# AnalogSupplies.net
KiCad netlist of a schematic drawn in Altium Designer
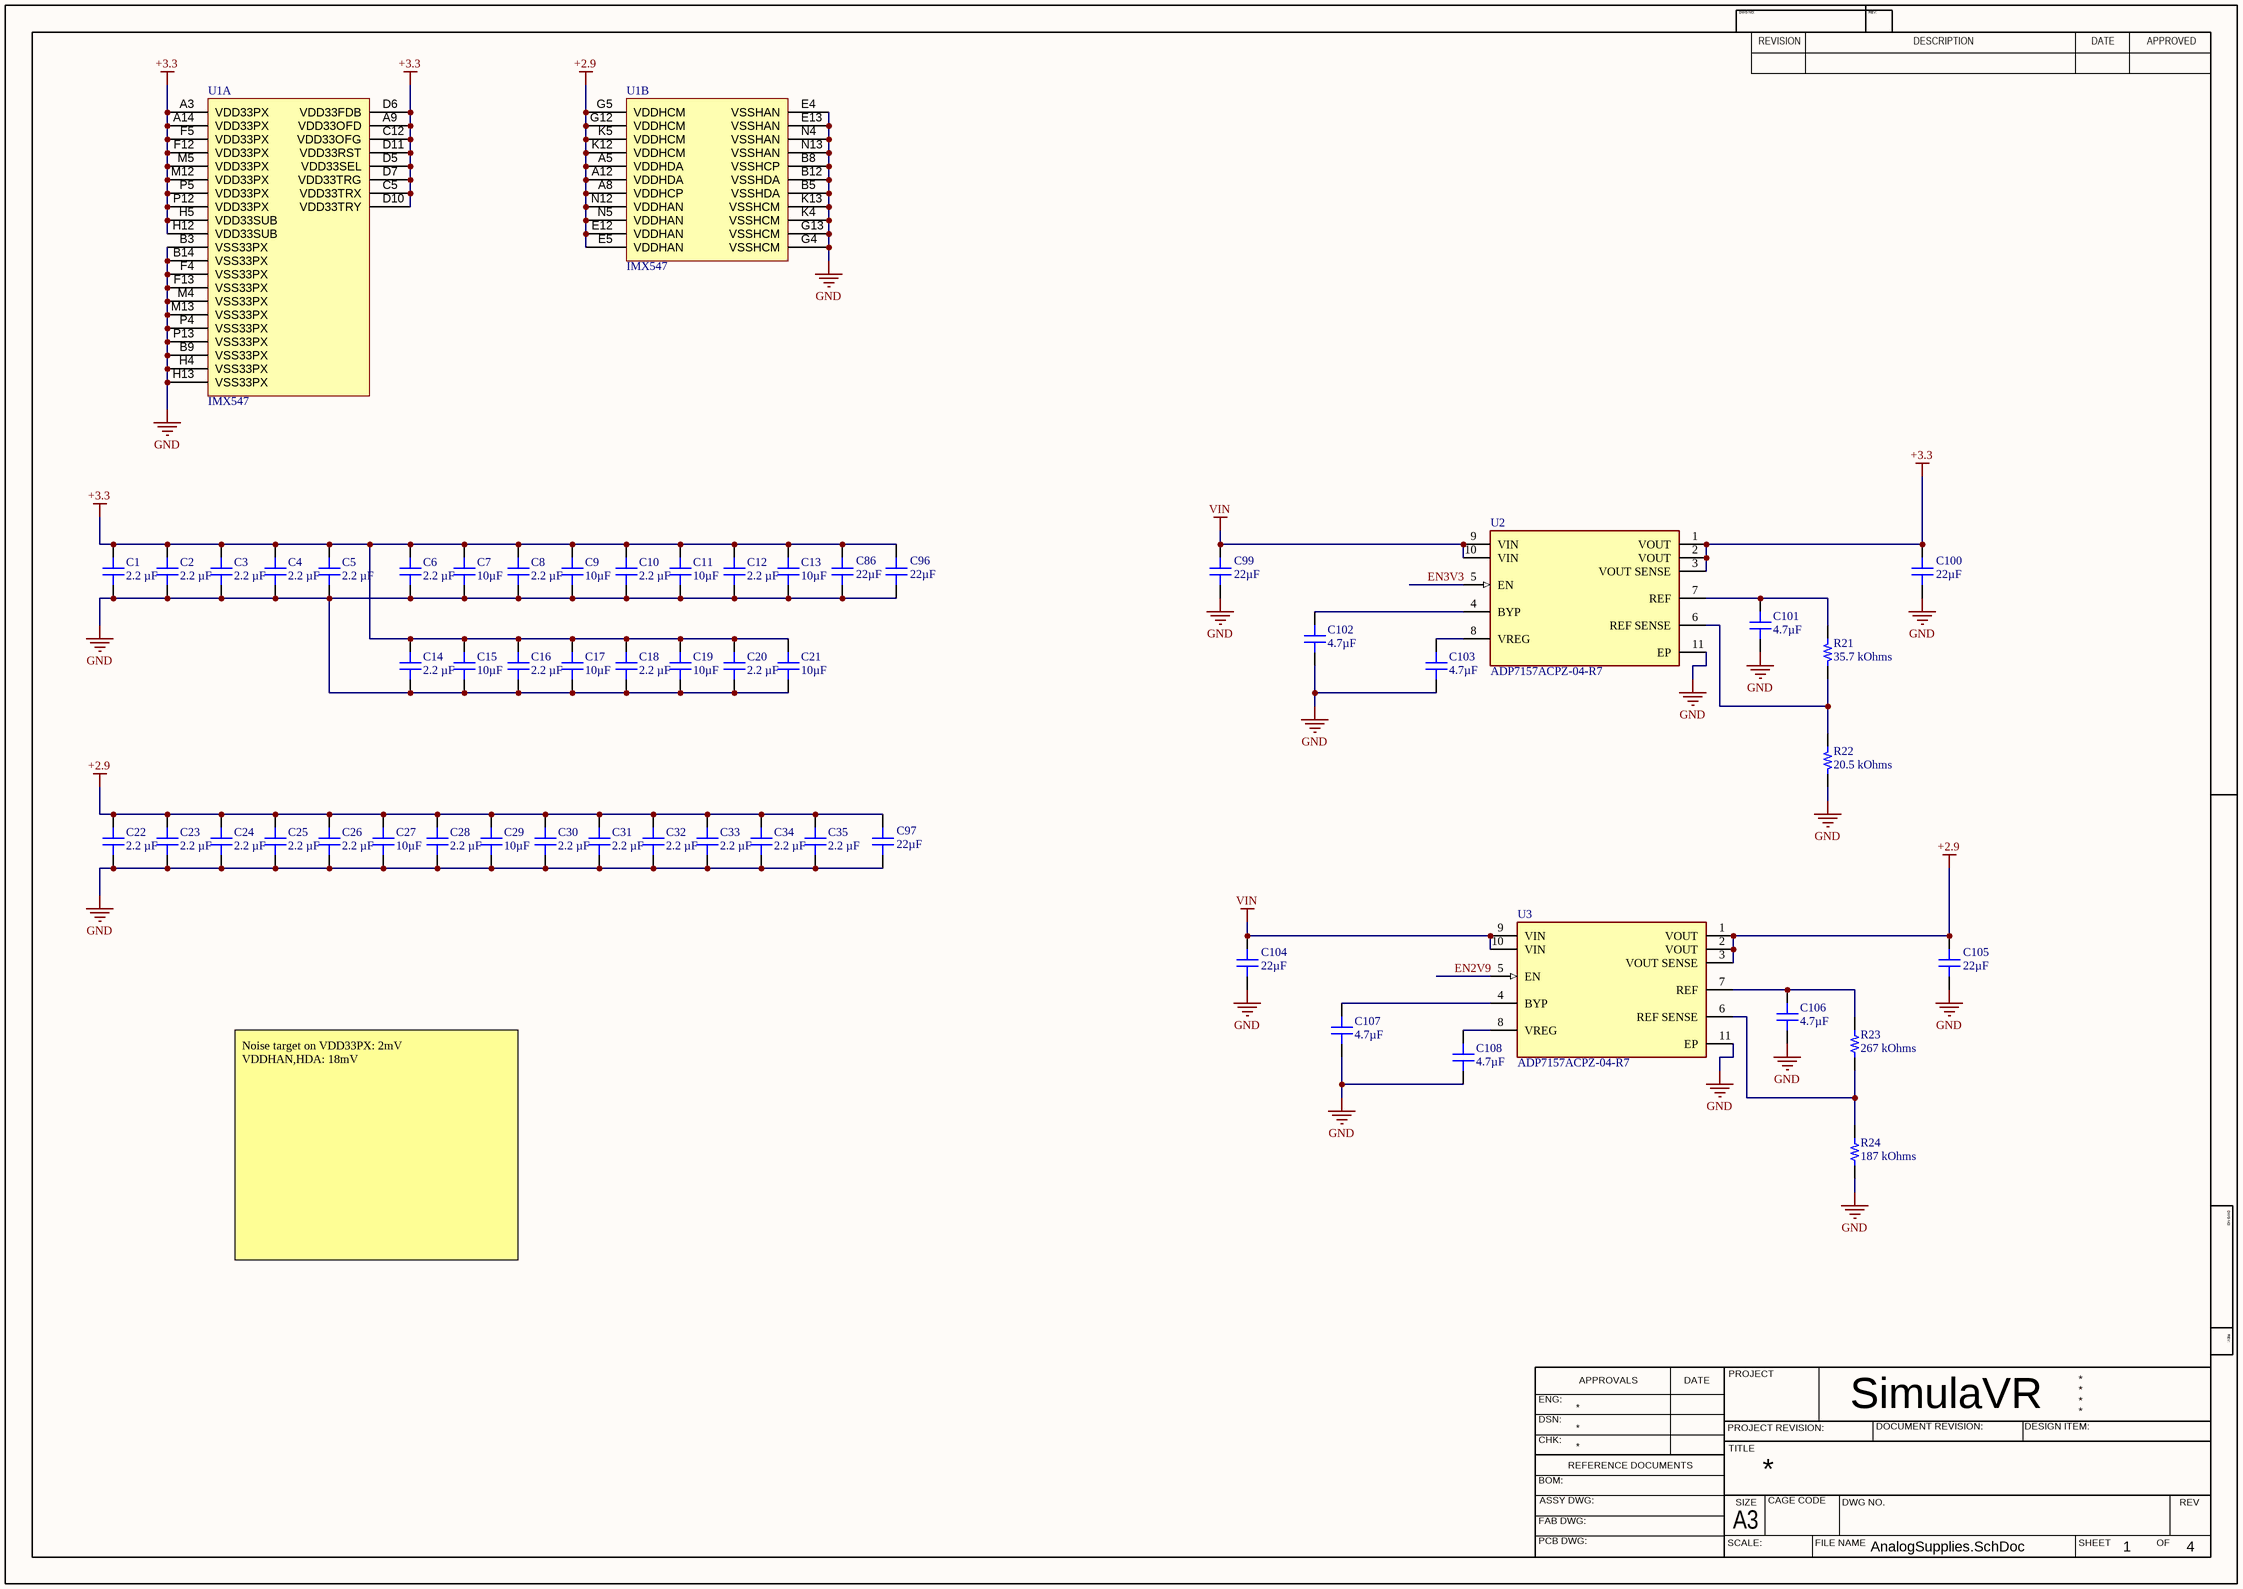
[diagram p0: AnalogSupplies.SchDoc]

(export (version "E")
  (design (tool "Eeschema 10.0.6"))
  (components
    (comp (ref "C1")
      (value "2.2 µF")
      (footprint "FP-GRM033-0_09-MFG")
      (description "CAP CER 2.2UF 6.3V X5R 0201")
      (fields
        (field (name "PART NUMBER") "GRM033R60J225ME01D")
        (field (name "MANUFACTURER") "Murata Electronics")
      )
      (libsource (lib "Celestial Altium Library - altium_library") (part "Capacitor"))
    )
    (comp (ref "C2")
      (value "2.2 µF")
      (footprint "FP-GRM033-0_09-MFG")
      (description "CAP CER 2.2UF 6.3V X5R 0201")
      (fields
        (field (name "PART NUMBER") "GRM033R60J225ME01D")
        (field (name "MANUFACTURER") "Murata Electronics")
      )
      (libsource (lib "Celestial Altium Library - altium_library") (part "Capacitor"))
    )
    (comp (ref "C3")
      (value "2.2 µF")
      (footprint "FP-GRM033-0_09-MFG")
      (description "CAP CER 2.2UF 6.3V X5R 0201")
      (fields
        (field (name "PART NUMBER") "GRM033R60J225ME01D")
        (field (name "MANUFACTURER") "Murata Electronics")
      )
      (libsource (lib "Celestial Altium Library - altium_library") (part "Capacitor"))
    )
    (comp (ref "C4")
      (value "2.2 µF")
      (footprint "FP-GRM033-0_09-MFG")
      (description "CAP CER 2.2UF 6.3V X5R 0201")
      (fields
        (field (name "PART NUMBER") "GRM033R60J225ME01D")
        (field (name "MANUFACTURER") "Murata Electronics")
      )
      (libsource (lib "Celestial Altium Library - altium_library") (part "Capacitor"))
    )
    (comp (ref "C5")
      (value "2.2 µF")
      (footprint "FP-GRM033-0_09-MFG")
      (description "CAP CER 2.2UF 6.3V X5R 0201")
      (fields
        (field (name "PART NUMBER") "GRM033R60J225ME01D")
        (field (name "MANUFACTURER") "Murata Electronics")
      )
      (libsource (lib "Celestial Altium Library - altium_library") (part "Capacitor"))
    )
    (comp (ref "C6")
      (value "2.2 µF")
      (footprint "FP-GRM033-0_09-MFG")
      (description "CAP CER 2.2UF 6.3V X5R 0201")
      (fields
        (field (name "PART NUMBER") "GRM033R60J225ME01D")
        (field (name "MANUFACTURER") "Murata Electronics")
      )
      (libsource (lib "Celestial Altium Library - altium_library") (part "Capacitor"))
    )
    (comp (ref "C7")
      (value "10µF")
      (footprint "FP-GRM188-0_15-MFG")
      (description "CAP CER 10UF 10V X5R 0603")
      (fields
        (field (name "PART NUMBER") "GRM188R61A106MAALD")
        (field (name "MANUFACTURER") "Murata Electronics")
      )
      (libsource (lib "Celestial Altium Library - altium_library") (part "Capacitor"))
    )
    (comp (ref "C8")
      (value "2.2 µF")
      (footprint "FP-GRM033-0_09-MFG")
      (description "CAP CER 2.2UF 6.3V X5R 0201")
      (fields
        (field (name "PART NUMBER") "GRM033R60J225ME01D")
        (field (name "MANUFACTURER") "Murata Electronics")
      )
      (libsource (lib "Celestial Altium Library - altium_library") (part "Capacitor"))
    )
    (comp (ref "C9")
      (value "10µF")
      (footprint "FP-GRM188-0_15-MFG")
      (description "CAP CER 10UF 10V X5R 0603")
      (fields
        (field (name "PART NUMBER") "GRM188R61A106MAALD")
        (field (name "MANUFACTURER") "Murata Electronics")
      )
      (libsource (lib "Celestial Altium Library - altium_library") (part "Capacitor"))
    )
    (comp (ref "C10")
      (value "2.2 µF")
      (footprint "FP-GRM033-0_09-MFG")
      (description "CAP CER 2.2UF 6.3V X5R 0201")
      (fields
        (field (name "PART NUMBER") "GRM033R60J225ME01D")
        (field (name "MANUFACTURER") "Murata Electronics")
      )
      (libsource (lib "Celestial Altium Library - altium_library") (part "Capacitor"))
    )
    (comp (ref "C11")
      (value "10µF")
      (footprint "FP-GRM188-0_15-MFG")
      (description "CAP CER 10UF 10V X5R 0603")
      (fields
        (field (name "PART NUMBER") "GRM188R61A106MAALD")
        (field (name "MANUFACTURER") "Murata Electronics")
      )
      (libsource (lib "Celestial Altium Library - altium_library") (part "Capacitor"))
    )
    (comp (ref "C12")
      (value "2.2 µF")
      (footprint "FP-GRM033-0_09-MFG")
      (description "CAP CER 2.2UF 6.3V X5R 0201")
      (fields
        (field (name "PART NUMBER") "GRM033R60J225ME01D")
        (field (name "MANUFACTURER") "Murata Electronics")
      )
      (libsource (lib "Celestial Altium Library - altium_library") (part "Capacitor"))
    )
    (comp (ref "C13")
      (value "10µF")
      (footprint "FP-GRM188-0_15-MFG")
      (description "CAP CER 10UF 10V X5R 0603")
      (fields
        (field (name "PART NUMBER") "GRM188R61A106MAALD")
        (field (name "MANUFACTURER") "Murata Electronics")
      )
      (libsource (lib "Celestial Altium Library - altium_library") (part "Capacitor"))
    )
    (comp (ref "C14")
      (value "2.2 µF")
      (footprint "FP-GRM033-0_09-MFG")
      (description "CAP CER 2.2UF 6.3V X5R 0201")
      (fields
        (field (name "PART NUMBER") "GRM033R60J225ME01D")
        (field (name "MANUFACTURER") "Murata Electronics")
      )
      (libsource (lib "Celestial Altium Library - altium_library") (part "Capacitor"))
    )
    (comp (ref "C15")
      (value "10µF")
      (footprint "FP-GRM188-0_15-MFG")
      (description "CAP CER 10UF 10V X5R 0603")
      (fields
        (field (name "PART NUMBER") "GRM188R61A106MAALD")
        (field (name "MANUFACTURER") "Murata Electronics")
      )
      (libsource (lib "Celestial Altium Library - altium_library") (part "Capacitor"))
    )
    (comp (ref "C16")
      (value "2.2 µF")
      (footprint "FP-GRM033-0_09-MFG")
      (description "CAP CER 2.2UF 6.3V X5R 0201")
      (fields
        (field (name "PART NUMBER") "GRM033R60J225ME01D")
        (field (name "MANUFACTURER") "Murata Electronics")
      )
      (libsource (lib "Celestial Altium Library - altium_library") (part "Capacitor"))
    )
    (comp (ref "C17")
      (value "10µF")
      (footprint "FP-GRM188-0_15-MFG")
      (description "CAP CER 10UF 10V X5R 0603")
      (fields
        (field (name "PART NUMBER") "GRM188R61A106MAALD")
        (field (name "MANUFACTURER") "Murata Electronics")
      )
      (libsource (lib "Celestial Altium Library - altium_library") (part "Capacitor"))
    )
    (comp (ref "C18")
      (value "2.2 µF")
      (footprint "FP-GRM033-0_09-MFG")
      (description "CAP CER 2.2UF 6.3V X5R 0201")
      (fields
        (field (name "PART NUMBER") "GRM033R60J225ME01D")
        (field (name "MANUFACTURER") "Murata Electronics")
      )
      (libsource (lib "Celestial Altium Library - altium_library") (part "Capacitor"))
    )
    (comp (ref "C19")
      (value "10µF")
      (footprint "FP-GRM188-0_15-MFG")
      (description "CAP CER 10UF 10V X5R 0603")
      (fields
        (field (name "PART NUMBER") "GRM188R61A106MAALD")
        (field (name "MANUFACTURER") "Murata Electronics")
      )
      (libsource (lib "Celestial Altium Library - altium_library") (part "Capacitor"))
    )
    (comp (ref "C20")
      (value "2.2 µF")
      (footprint "FP-GRM033-0_09-MFG")
      (description "CAP CER 2.2UF 6.3V X5R 0201")
      (fields
        (field (name "PART NUMBER") "GRM033R60J225ME01D")
        (field (name "MANUFACTURER") "Murata Electronics")
      )
      (libsource (lib "Celestial Altium Library - altium_library") (part "Capacitor"))
    )
    (comp (ref "C21")
      (value "10µF")
      (footprint "FP-GRM188-0_15-MFG")
      (description "CAP CER 10UF 10V X5R 0603")
      (fields
        (field (name "PART NUMBER") "GRM188R61A106MAALD")
        (field (name "MANUFACTURER") "Murata Electronics")
      )
      (libsource (lib "Celestial Altium Library - altium_library") (part "Capacitor"))
    )
    (comp (ref "C22")
      (value "2.2 µF")
      (footprint "FP-GRM033-0_09-MFG")
      (description "CAP CER 2.2UF 6.3V X5R 0201")
      (fields
        (field (name "PART NUMBER") "GRM033R60J225ME01D")
        (field (name "MANUFACTURER") "Murata Electronics")
      )
      (libsource (lib "Celestial Altium Library - altium_library") (part "Capacitor"))
    )
    (comp (ref "C23")
      (value "2.2 µF")
      (footprint "FP-GRM033-0_09-MFG")
      (description "CAP CER 2.2UF 6.3V X5R 0201")
      (fields
        (field (name "PART NUMBER") "GRM033R60J225ME01D")
        (field (name "MANUFACTURER") "Murata Electronics")
      )
      (libsource (lib "Celestial Altium Library - altium_library") (part "Capacitor"))
    )
    (comp (ref "C24")
      (value "2.2 µF")
      (footprint "FP-GRM033-0_09-MFG")
      (description "CAP CER 2.2UF 6.3V X5R 0201")
      (fields
        (field (name "PART NUMBER") "GRM033R60J225ME01D")
        (field (name "MANUFACTURER") "Murata Electronics")
      )
      (libsource (lib "Celestial Altium Library - altium_library") (part "Capacitor"))
    )
    (comp (ref "C25")
      (value "2.2 µF")
      (footprint "FP-GRM033-0_09-MFG")
      (description "CAP CER 2.2UF 6.3V X5R 0201")
      (fields
        (field (name "PART NUMBER") "GRM033R60J225ME01D")
        (field (name "MANUFACTURER") "Murata Electronics")
      )
      (libsource (lib "Celestial Altium Library - altium_library") (part "Capacitor"))
    )
    (comp (ref "C26")
      (value "2.2 µF")
      (footprint "FP-GRM033-0_09-MFG")
      (description "CAP CER 2.2UF 6.3V X5R 0201")
      (fields
        (field (name "PART NUMBER") "GRM033R60J225ME01D")
        (field (name "MANUFACTURER") "Murata Electronics")
      )
      (libsource (lib "Celestial Altium Library - altium_library") (part "Capacitor"))
    )
    (comp (ref "C27")
      (value "10µF")
      (footprint "FP-GRM188-0_15-MFG")
      (description "CAP CER 10UF 10V X5R 0603")
      (fields
        (field (name "PART NUMBER") "GRM188R61A106MAALD")
        (field (name "MANUFACTURER") "Murata Electronics")
      )
      (libsource (lib "Celestial Altium Library - altium_library") (part "Capacitor"))
    )
    (comp (ref "C28")
      (value "2.2 µF")
      (footprint "FP-GRM033-0_09-MFG")
      (description "CAP CER 2.2UF 6.3V X5R 0201")
      (fields
        (field (name "PART NUMBER") "GRM033R60J225ME01D")
        (field (name "MANUFACTURER") "Murata Electronics")
      )
      (libsource (lib "Celestial Altium Library - altium_library") (part "Capacitor"))
    )
    (comp (ref "C29")
      (value "10µF")
      (footprint "FP-GRM188-0_15-MFG")
      (description "CAP CER 10UF 10V X5R 0603")
      (fields
        (field (name "PART NUMBER") "GRM188R61A106MAALD")
        (field (name "MANUFACTURER") "Murata Electronics")
      )
      (libsource (lib "Celestial Altium Library - altium_library") (part "Capacitor"))
    )
    (comp (ref "C30")
      (value "2.2 µF")
      (footprint "FP-GRM033-0_09-MFG")
      (description "CAP CER 2.2UF 6.3V X5R 0201")
      (fields
        (field (name "PART NUMBER") "GRM033R60J225ME01D")
        (field (name "MANUFACTURER") "Murata Electronics")
      )
      (libsource (lib "Celestial Altium Library - altium_library") (part "Capacitor"))
    )
    (comp (ref "C31")
      (value "2.2 µF")
      (footprint "FP-GRM033-0_09-MFG")
      (description "CAP CER 2.2UF 6.3V X5R 0201")
      (fields
        (field (name "PART NUMBER") "GRM033R60J225ME01D")
        (field (name "MANUFACTURER") "Murata Electronics")
      )
      (libsource (lib "Celestial Altium Library - altium_library") (part "Capacitor"))
    )
    (comp (ref "C32")
      (value "2.2 µF")
      (footprint "FP-GRM033-0_09-MFG")
      (description "CAP CER 2.2UF 6.3V X5R 0201")
      (fields
        (field (name "PART NUMBER") "GRM033R60J225ME01D")
        (field (name "MANUFACTURER") "Murata Electronics")
      )
      (libsource (lib "Celestial Altium Library - altium_library") (part "Capacitor"))
    )
    (comp (ref "C33")
      (value "2.2 µF")
      (footprint "FP-GRM033-0_09-MFG")
      (description "CAP CER 2.2UF 6.3V X5R 0201")
      (fields
        (field (name "PART NUMBER") "GRM033R60J225ME01D")
        (field (name "MANUFACTURER") "Murata Electronics")
      )
      (libsource (lib "Celestial Altium Library - altium_library") (part "Capacitor"))
    )
    (comp (ref "C34")
      (value "2.2 µF")
      (footprint "FP-GRM033-0_09-MFG")
      (description "CAP CER 2.2UF 6.3V X5R 0201")
      (fields
        (field (name "PART NUMBER") "GRM033R60J225ME01D")
        (field (name "MANUFACTURER") "Murata Electronics")
      )
      (libsource (lib "Celestial Altium Library - altium_library") (part "Capacitor"))
    )
    (comp (ref "C35")
      (value "2.2 µF")
      (footprint "FP-GRM033-0_09-MFG")
      (description "CAP CER 2.2UF 6.3V X5R 0201")
      (fields
        (field (name "PART NUMBER") "GRM033R60J225ME01D")
        (field (name "MANUFACTURER") "Murata Electronics")
      )
      (libsource (lib "Celestial Altium Library - altium_library") (part "Capacitor"))
    )
    (comp (ref "C86")
      (value "22µF")
      (footprint "FP-GRM21B-0_2-e0_2_0_7-MFG")
      (description "CAP CER 22UF 10V X5R 0805")
      (fields
        (field (name "PART NUMBER") "GRM21BR61A226ME44L")
        (field (name "MANUFACTURER") "Murata Electronics")
      )
      (libsource (lib "Celestial Altium Library - altium_library") (part "Capacitor"))
    )
    (comp (ref "C96")
      (value "22µF")
      (footprint "FP-GRM21B-0_2-e0_2_0_7-MFG")
      (description "CAP CER 22UF 10V X5R 0805")
      (fields
        (field (name "PART NUMBER") "GRM21BR61A226ME44L")
        (field (name "MANUFACTURER") "Murata Electronics")
      )
      (libsource (lib "Celestial Altium Library - altium_library") (part "Capacitor"))
    )
    (comp (ref "C97")
      (value "22µF")
      (footprint "FP-GRM21B-0_2-e0_2_0_7-MFG")
      (description "CAP CER 22UF 10V X5R 0805")
      (fields
        (field (name "PART NUMBER") "GRM21BR61A226ME44L")
        (field (name "MANUFACTURER") "Murata Electronics")
      )
      (libsource (lib "Celestial Altium Library - altium_library") (part "Capacitor"))
    )
    (comp (ref "C99")
      (value "22µF")
      (footprint "FP-GRM21B-0_2-e0_2_0_7-MFG")
      (description "CAP CER 22UF 10V X5R 0805")
      (fields
        (field (name "PART NUMBER") "GRM21BR61A226ME44L")
        (field (name "MANUFACTURER") "Murata Electronics")
      )
      (libsource (lib "Celestial Altium Library - altium_library") (part "Capacitor"))
    )
    (comp (ref "C100")
      (value "22µF")
      (footprint "FP-GRM21B-0_2-e0_2_0_7-MFG")
      (description "CAP CER 22UF 10V X5R 0805")
      (fields
        (field (name "PART NUMBER") "GRM21BR61A226ME44L")
        (field (name "MANUFACTURER") "Murata Electronics")
      )
      (libsource (lib "Celestial Altium Library - altium_library") (part "Capacitor"))
    )
    (comp (ref "C101")
      (value "4.7µF")
      (footprint "FP-GRM155-0_15-MFG")
      (description "CAP CER 4.7UF 10V X5R 0402")
      (fields
        (field (name "PART NUMBER") "GRM155R61A475MEAAD")
        (field (name "MANUFACTURER") "Murata Electronics")
      )
      (libsource (lib "Celestial Altium Library - altium_library") (part "Capacitor"))
    )
    (comp (ref "C102")
      (value "4.7µF")
      (footprint "FP-GRM155-0_15-MFG")
      (description "CAP CER 4.7UF 10V X5R 0402")
      (fields
        (field (name "PART NUMBER") "GRM155R61A475MEAAD")
        (field (name "MANUFACTURER") "Murata Electronics")
      )
      (libsource (lib "Celestial Altium Library - altium_library") (part "Capacitor"))
    )
    (comp (ref "C103")
      (value "4.7µF")
      (footprint "FP-GRM155-0_15-MFG")
      (description "CAP CER 4.7UF 10V X5R 0402")
      (fields
        (field (name "PART NUMBER") "GRM155R61A475MEAAD")
        (field (name "MANUFACTURER") "Murata Electronics")
      )
      (libsource (lib "Celestial Altium Library - altium_library") (part "Capacitor"))
    )
    (comp (ref "C104")
      (value "22µF")
      (footprint "FP-GRM21B-0_2-e0_2_0_7-MFG")
      (description "CAP CER 22UF 10V X5R 0805")
      (fields
        (field (name "PART NUMBER") "GRM21BR61A226ME44L")
        (field (name "MANUFACTURER") "Murata Electronics")
      )
      (libsource (lib "Celestial Altium Library - altium_library") (part "Capacitor"))
    )
    (comp (ref "C105")
      (value "22µF")
      (footprint "FP-GRM21B-0_2-e0_2_0_7-MFG")
      (description "CAP CER 22UF 10V X5R 0805")
      (fields
        (field (name "PART NUMBER") "GRM21BR61A226ME44L")
        (field (name "MANUFACTURER") "Murata Electronics")
      )
      (libsource (lib "Celestial Altium Library - altium_library") (part "Capacitor"))
    )
    (comp (ref "C106")
      (value "4.7µF")
      (footprint "FP-GRM155-0_15-MFG")
      (description "CAP CER 4.7UF 10V X5R 0402")
      (fields
        (field (name "PART NUMBER") "GRM155R61A475MEAAD")
        (field (name "MANUFACTURER") "Murata Electronics")
      )
      (libsource (lib "Celestial Altium Library - altium_library") (part "Capacitor"))
    )
    (comp (ref "C107")
      (value "4.7µF")
      (footprint "FP-GRM155-0_15-MFG")
      (description "CAP CER 4.7UF 10V X5R 0402")
      (fields
        (field (name "PART NUMBER") "GRM155R61A475MEAAD")
        (field (name "MANUFACTURER") "Murata Electronics")
      )
      (libsource (lib "Celestial Altium Library - altium_library") (part "Capacitor"))
    )
    (comp (ref "C108")
      (value "4.7µF")
      (footprint "FP-GRM155-0_15-MFG")
      (description "CAP CER 4.7UF 10V X5R 0402")
      (fields
        (field (name "PART NUMBER") "GRM155R61A475MEAAD")
        (field (name "MANUFACTURER") "Murata Electronics")
      )
      (libsource (lib "Celestial Altium Library - altium_library") (part "Capacitor"))
    )
    (comp (ref "R21")
      (value "35.7 kOhms")
      (footprint "RES 0201_0603")
      (description "RES SMD 35.7K OHM 1% 1/20W 0201")
      (fields
        (field (name "PART NUMBER") "ERJ-1GNF3572C")
        (field (name "MANUFACTURER") "Panasonic Electronic Components")
      )
      (libsource (lib "Celestial Altium Library - altium_library") (part "Resistor"))
    )
    (comp (ref "R22")
      (value "20.5 kOhms")
      (footprint "RES 0201_0603")
      (description "RES SMD 20.5K OHM 1% 1/20W 0201")
      (fields
        (field (name "PART NUMBER") "ERJ-1GNF2052C")
        (field (name "MANUFACTURER") "Panasonic Electronic Components")
      )
      (libsource (lib "Celestial Altium Library - altium_library") (part "Resistor"))
    )
    (comp (ref "R23")
      (value "267 kOhms")
      (footprint "RES 0201_0603")
      (description "RES 267K OHM 1% 1/20W 0201")
      (fields (field (name "PART NUMBER") "RC0201FR-07267KL") (field (name "MANUFACTURER") "Yageo"))
      (libsource (lib "Celestial Altium Library - altium_library") (part "Resistor"))
    )
    (comp (ref "R24")
      (value "187 kOhms")
      (footprint "RES 0201_0603")
      (description "RES SMD 187K OHM 1% 1/20W 0201")
      (fields
        (field (name "PART NUMBER") "ERJ-1GNF1873C")
        (field (name "MANUFACTURER") "Panasonic Electronic Components")
      )
      (libsource (lib "Celestial Altium Library - altium_library") (part "Resistor"))
    )
    (comp (ref "U1")
      (value "IMX547")
      (footprint "LGA230C100P16X17_1680X2000X260")
      (description "Sony IMX547 sensor")
      (libsource (lib "David Kräutmann Beratung") (part "IMX547"))
    )
    (comp (ref "U2")
      (value "ADP7157ACPZ-04-R7")
      (footprint "FP-CP-10-9-IPC_B")
      (description "LDO Regulator Pos 1.2V to 3.3V 1.2A 10-Pin LFCSP EP T/R")
      (libsource (lib "SimulaVR") (part "c7b0ea321eafad26d909bd2019a0797"))
    )
    (comp (ref "U3")
      (value "ADP7157ACPZ-04-R7")
      (footprint "FP-CP-10-9-IPC_B")
      (description "LDO Regulator Pos 1.2V to 3.3V 1.2A 10-Pin LFCSP EP T/R")
      (libsource (lib "SimulaVR") (part "c7b0ea321eafad26d909bd2019a0797"))
    )
  )
  (nets
    (net (code "1") (name "+2.9") (class "Default")
      (node (ref "C105") (pin "1") (pinfunction "1_1") (pintype "passive"))
      (node (ref "C22") (pin "2") (pinfunction "2_2") (pintype "passive"))
      (node (ref "C23") (pin "2") (pinfunction "2_2") (pintype "passive"))
      (node (ref "C24") (pin "2") (pinfunction "2_2") (pintype "passive"))
      (node (ref "C25") (pin "2") (pinfunction "2_2") (pintype "passive"))
      (node (ref "C26") (pin "2") (pinfunction "2_2") (pintype "passive"))
      (node (ref "C27") (pin "2") (pinfunction "2_2") (pintype "passive"))
      (node (ref "C28") (pin "2") (pinfunction "2_2") (pintype "passive"))
      (node (ref "C29") (pin "2") (pinfunction "2_2") (pintype "passive"))
      (node (ref "C30") (pin "2") (pinfunction "2_2") (pintype "passive"))
      (node (ref "C31") (pin "2") (pinfunction "2_2") (pintype "passive"))
      (node (ref "C32") (pin "2") (pinfunction "2_2") (pintype "passive"))
      (node (ref "C33") (pin "2") (pinfunction "2_2") (pintype "passive"))
      (node (ref "C34") (pin "2") (pinfunction "2_2") (pintype "passive"))
      (node (ref "C35") (pin "2") (pinfunction "2_2") (pintype "passive"))
      (node (ref "C97") (pin "1") (pinfunction "1_1") (pintype "passive"))
      (node (ref "U1") (pin "A12") (pinfunction "VDDHDA_A12") (pintype "power_in"))
      (node (ref "U1") (pin "A5") (pinfunction "VDDHDA_A5") (pintype "power_in"))
      (node (ref "U1") (pin "A8") (pinfunction "VDDHCP_A8") (pintype "power_in"))
      (node (ref "U1") (pin "E12") (pinfunction "VDDHAN_E12") (pintype "power_in"))
      (node (ref "U1") (pin "E5") (pinfunction "VDDHAN_E5") (pintype "power_in"))
      (node (ref "U1") (pin "G12") (pinfunction "VDDHCM_G12") (pintype "power_in"))
      (node (ref "U1") (pin "G5") (pinfunction "VDDHCM_G5") (pintype "power_in"))
      (node (ref "U1") (pin "K12") (pinfunction "VDDHCM_K12") (pintype "power_in"))
      (node (ref "U1") (pin "K5") (pinfunction "VDDHCM_K5") (pintype "power_in"))
      (node (ref "U1") (pin "N12") (pinfunction "VDDHAN_N12") (pintype "power_in"))
      (node (ref "U1") (pin "N5") (pinfunction "VDDHAN_N5") (pintype "power_in"))
      (node (ref "U3") (pin "1") (pinfunction "VOUT_1") (pintype "power_in"))
      (node (ref "U3") (pin "2") (pinfunction "VOUT_2") (pintype "power_in"))
      (node (ref "U3") (pin "3") (pinfunction "VOUT_SENSE_3") (pintype "power_in"))
    )
    (net (code "2") (name "+3.3") (class "Default")
      (node (ref "C1") (pin "2") (pinfunction "2_2") (pintype "passive"))
      (node (ref "C10") (pin "2") (pinfunction "2_2") (pintype "passive"))
      (node (ref "C100") (pin "1") (pinfunction "1_1") (pintype "passive"))
      (node (ref "C11") (pin "2") (pinfunction "2_2") (pintype "passive"))
      (node (ref "C12") (pin "2") (pinfunction "2_2") (pintype "passive"))
      (node (ref "C13") (pin "2") (pinfunction "2_2") (pintype "passive"))
      (node (ref "C14") (pin "2") (pinfunction "2_2") (pintype "passive"))
      (node (ref "C15") (pin "2") (pinfunction "2_2") (pintype "passive"))
      (node (ref "C16") (pin "2") (pinfunction "2_2") (pintype "passive"))
      (node (ref "C17") (pin "2") (pinfunction "2_2") (pintype "passive"))
      (node (ref "C18") (pin "2") (pinfunction "2_2") (pintype "passive"))
      (node (ref "C19") (pin "2") (pinfunction "2_2") (pintype "passive"))
      (node (ref "C2") (pin "2") (pinfunction "2_2") (pintype "passive"))
      (node (ref "C20") (pin "2") (pinfunction "2_2") (pintype "passive"))
      (node (ref "C21") (pin "2") (pinfunction "2_2") (pintype "passive"))
      (node (ref "C3") (pin "2") (pinfunction "2_2") (pintype "passive"))
      (node (ref "C4") (pin "2") (pinfunction "2_2") (pintype "passive"))
      (node (ref "C5") (pin "2") (pinfunction "2_2") (pintype "passive"))
      (node (ref "C6") (pin "2") (pinfunction "2_2") (pintype "passive"))
      (node (ref "C7") (pin "2") (pinfunction "2_2") (pintype "passive"))
      (node (ref "C8") (pin "2") (pinfunction "2_2") (pintype "passive"))
      (node (ref "C86") (pin "1") (pinfunction "1_1") (pintype "passive"))
      (node (ref "C9") (pin "2") (pinfunction "2_2") (pintype "passive"))
      (node (ref "C96") (pin "1") (pinfunction "1_1") (pintype "passive"))
      (node (ref "U1") (pin "A14") (pinfunction "VDD33PX_A14") (pintype "power_in"))
      (node (ref "U1") (pin "A3") (pinfunction "VDD33PX_A3") (pintype "power_in"))
      (node (ref "U1") (pin "A9") (pinfunction "VDD33OFD_A9") (pintype "power_in"))
      (node (ref "U1") (pin "C12") (pinfunction "VDD33OFG_C12") (pintype "power_in"))
      (node (ref "U1") (pin "C5") (pinfunction "VDD33TRX_C5") (pintype "power_in"))
      (node (ref "U1") (pin "D10") (pinfunction "VDD33TRY_D10") (pintype "power_in"))
      (node (ref "U1") (pin "D11") (pinfunction "VDD33RST_D11") (pintype "power_in"))
      (node (ref "U1") (pin "D5") (pinfunction "VDD33SEL_D5") (pintype "power_in"))
      (node (ref "U1") (pin "D6") (pinfunction "VDD33FDB_D6") (pintype "power_in"))
      (node (ref "U1") (pin "D7") (pinfunction "VDD33TRG_D7") (pintype "power_in"))
      (node (ref "U1") (pin "F12") (pinfunction "VDD33PX_F12") (pintype "power_in"))
      (node (ref "U1") (pin "F5") (pinfunction "VDD33PX_F5") (pintype "power_in"))
      (node (ref "U1") (pin "H12") (pinfunction "VDD33SUB_H12") (pintype "power_in"))
      (node (ref "U1") (pin "H5") (pinfunction "VDD33SUB_H5") (pintype "power_in"))
      (node (ref "U1") (pin "M12") (pinfunction "VDD33PX_M12") (pintype "power_in"))
      (node (ref "U1") (pin "M5") (pinfunction "VDD33PX_M5") (pintype "power_in"))
      (node (ref "U1") (pin "P12") (pinfunction "VDD33PX_P12") (pintype "power_in"))
      (node (ref "U1") (pin "P5") (pinfunction "VDD33PX_P5") (pintype "power_in"))
      (node (ref "U2") (pin "1") (pinfunction "VOUT_1") (pintype "power_in"))
      (node (ref "U2") (pin "2") (pinfunction "VOUT_2") (pintype "power_in"))
      (node (ref "U2") (pin "3") (pinfunction "VOUT_SENSE_3") (pintype "power_in"))
    )
    (net (code "3") (name "/EN2V9") (class "Default")
      (node (ref "U3") (pin "5") (pinfunction "EN_5") (pintype "input"))
    )
    (net (code "4") (name "/EN3V3") (class "Default")
      (node (ref "U2") (pin "5") (pinfunction "EN_5") (pintype "input"))
    )
    (net (code "5") (name "GND") (class "Default")
      (node (ref "C1") (pin "1") (pinfunction "1_1") (pintype "passive"))
      (node (ref "C10") (pin "1") (pinfunction "1_1") (pintype "passive"))
      (node (ref "C100") (pin "2") (pinfunction "2_2") (pintype "passive"))
      (node (ref "C101") (pin "1") (pinfunction "1_1") (pintype "passive"))
      (node (ref "C102") (pin "1") (pinfunction "1_1") (pintype "passive"))
      (node (ref "C103") (pin "1") (pinfunction "1_1") (pintype "passive"))
      (node (ref "C104") (pin "2") (pinfunction "2_2") (pintype "passive"))
      (node (ref "C105") (pin "2") (pinfunction "2_2") (pintype "passive"))
      (node (ref "C106") (pin "1") (pinfunction "1_1") (pintype "passive"))
      (node (ref "C107") (pin "1") (pinfunction "1_1") (pintype "passive"))
      (node (ref "C108") (pin "1") (pinfunction "1_1") (pintype "passive"))
      (node (ref "C11") (pin "1") (pinfunction "1_1") (pintype "passive"))
      (node (ref "C12") (pin "1") (pinfunction "1_1") (pintype "passive"))
      (node (ref "C13") (pin "1") (pinfunction "1_1") (pintype "passive"))
      (node (ref "C14") (pin "1") (pinfunction "1_1") (pintype "passive"))
      (node (ref "C15") (pin "1") (pinfunction "1_1") (pintype "passive"))
      (node (ref "C16") (pin "1") (pinfunction "1_1") (pintype "passive"))
      (node (ref "C17") (pin "1") (pinfunction "1_1") (pintype "passive"))
      (node (ref "C18") (pin "1") (pinfunction "1_1") (pintype "passive"))
      (node (ref "C19") (pin "1") (pinfunction "1_1") (pintype "passive"))
      (node (ref "C2") (pin "1") (pinfunction "1_1") (pintype "passive"))
      (node (ref "C20") (pin "1") (pinfunction "1_1") (pintype "passive"))
      (node (ref "C21") (pin "1") (pinfunction "1_1") (pintype "passive"))
      (node (ref "C22") (pin "1") (pinfunction "1_1") (pintype "passive"))
      (node (ref "C23") (pin "1") (pinfunction "1_1") (pintype "passive"))
      (node (ref "C24") (pin "1") (pinfunction "1_1") (pintype "passive"))
      (node (ref "C25") (pin "1") (pinfunction "1_1") (pintype "passive"))
      (node (ref "C26") (pin "1") (pinfunction "1_1") (pintype "passive"))
      (node (ref "C27") (pin "1") (pinfunction "1_1") (pintype "passive"))
      (node (ref "C28") (pin "1") (pinfunction "1_1") (pintype "passive"))
      (node (ref "C29") (pin "1") (pinfunction "1_1") (pintype "passive"))
      (node (ref "C3") (pin "1") (pinfunction "1_1") (pintype "passive"))
      (node (ref "C30") (pin "1") (pinfunction "1_1") (pintype "passive"))
      (node (ref "C31") (pin "1") (pinfunction "1_1") (pintype "passive"))
      (node (ref "C32") (pin "1") (pinfunction "1_1") (pintype "passive"))
      (node (ref "C33") (pin "1") (pinfunction "1_1") (pintype "passive"))
      (node (ref "C34") (pin "1") (pinfunction "1_1") (pintype "passive"))
      (node (ref "C35") (pin "1") (pinfunction "1_1") (pintype "passive"))
      (node (ref "C4") (pin "1") (pinfunction "1_1") (pintype "passive"))
      (node (ref "C5") (pin "1") (pinfunction "1_1") (pintype "passive"))
      (node (ref "C6") (pin "1") (pinfunction "1_1") (pintype "passive"))
      (node (ref "C7") (pin "1") (pinfunction "1_1") (pintype "passive"))
      (node (ref "C8") (pin "1") (pinfunction "1_1") (pintype "passive"))
      (node (ref "C86") (pin "2") (pinfunction "2_2") (pintype "passive"))
      (node (ref "C9") (pin "1") (pinfunction "1_1") (pintype "passive"))
      (node (ref "C96") (pin "2") (pinfunction "2_2") (pintype "passive"))
      (node (ref "C97") (pin "2") (pinfunction "2_2") (pintype "passive"))
      (node (ref "C99") (pin "2") (pinfunction "2_2") (pintype "passive"))
      (node (ref "R22") (pin "1") (pinfunction "1_1") (pintype "passive"))
      (node (ref "R24") (pin "1") (pinfunction "1_1") (pintype "passive"))
      (node (ref "U1") (pin "B12") (pinfunction "VSSHDA_B12") (pintype "power_in"))
      (node (ref "U1") (pin "B14") (pinfunction "VSS33PX_B14") (pintype "power_in"))
      (node (ref "U1") (pin "B3") (pinfunction "VSS33PX_B3") (pintype "power_in"))
      (node (ref "U1") (pin "B5") (pinfunction "VSSHDA_B5") (pintype "power_in"))
      (node (ref "U1") (pin "B8") (pinfunction "VSSHCP_B8") (pintype "power_in"))
      (node (ref "U1") (pin "B9") (pinfunction "VSS33PX_B9") (pintype "power_in"))
      (node (ref "U1") (pin "E13") (pinfunction "VSSHAN_E13") (pintype "power_in"))
      (node (ref "U1") (pin "E4") (pinfunction "VSSHAN_E4") (pintype "power_in"))
      (node (ref "U1") (pin "F13") (pinfunction "VSS33PX_F13") (pintype "power_in"))
      (node (ref "U1") (pin "F4") (pinfunction "VSS33PX_F4") (pintype "power_in"))
      (node (ref "U1") (pin "G13") (pinfunction "VSSHCM_G13") (pintype "power_in"))
      (node (ref "U1") (pin "G4") (pinfunction "VSSHCM_G4") (pintype "power_in"))
      (node (ref "U1") (pin "H13") (pinfunction "VSS33PX_H13") (pintype "power_in"))
      (node (ref "U1") (pin "H4") (pinfunction "VSS33PX_H4") (pintype "power_in"))
      (node (ref "U1") (pin "K13") (pinfunction "VSSHCM_K13") (pintype "power_in"))
      (node (ref "U1") (pin "K4") (pinfunction "VSSHCM_K4") (pintype "power_in"))
      (node (ref "U1") (pin "M13") (pinfunction "VSS33PX_M13") (pintype "power_in"))
      (node (ref "U1") (pin "M4") (pinfunction "VSS33PX_M4") (pintype "power_in"))
      (node (ref "U1") (pin "N13") (pinfunction "VSSHAN_N13") (pintype "power_in"))
      (node (ref "U1") (pin "N4") (pinfunction "VSSHAN_N4") (pintype "power_in"))
      (node (ref "U1") (pin "P13") (pinfunction "VSS33PX_P13") (pintype "power_in"))
      (node (ref "U1") (pin "P4") (pinfunction "VSS33PX_P4") (pintype "power_in"))
      (node (ref "U2") (pin "11") (pinfunction "EP_11") (pintype "power_in"))
      (node (ref "U3") (pin "11") (pinfunction "EP_11") (pintype "power_in"))
    )
    (net (code "6") (name "Net-(U2-BYP)") (class "Default")
      (node (ref "C102") (pin "2") (pinfunction "2_2") (pintype "passive"))
      (node (ref "U2") (pin "4") (pinfunction "BYP_4") (pintype "passive"))
    )
    (net (code "7") (name "Net-(U2-REF)") (class "Default")
      (node (ref "C101") (pin "2") (pinfunction "2_2") (pintype "passive"))
      (node (ref "R21") (pin "2") (pinfunction "2_2") (pintype "passive"))
      (node (ref "U2") (pin "7") (pinfunction "REF_7") (pintype "power_in"))
    )
    (net (code "8") (name "Net-(U2-REF_SENSE)") (class "Default")
      (node (ref "R21") (pin "1") (pinfunction "1_1") (pintype "passive"))
      (node (ref "R22") (pin "2") (pinfunction "2_2") (pintype "passive"))
      (node (ref "U2") (pin "6") (pinfunction "REF_SENSE_6") (pintype "power_in"))
    )
    (net (code "9") (name "Net-(U2-VREG)") (class "Default")
      (node (ref "C103") (pin "2") (pinfunction "2_2") (pintype "passive"))
      (node (ref "U2") (pin "8") (pinfunction "VREG_8") (pintype "power_in"))
    )
    (net (code "10") (name "Net-(U3-BYP)") (class "Default")
      (node (ref "C107") (pin "2") (pinfunction "2_2") (pintype "passive"))
      (node (ref "U3") (pin "4") (pinfunction "BYP_4") (pintype "passive"))
    )
    (net (code "11") (name "Net-(U3-REF)") (class "Default")
      (node (ref "C106") (pin "2") (pinfunction "2_2") (pintype "passive"))
      (node (ref "R23") (pin "2") (pinfunction "2_2") (pintype "passive"))
      (node (ref "U3") (pin "7") (pinfunction "REF_7") (pintype "power_in"))
    )
    (net (code "12") (name "Net-(U3-REF_SENSE)") (class "Default")
      (node (ref "R23") (pin "1") (pinfunction "1_1") (pintype "passive"))
      (node (ref "R24") (pin "2") (pinfunction "2_2") (pintype "passive"))
      (node (ref "U3") (pin "6") (pinfunction "REF_SENSE_6") (pintype "power_in"))
    )
    (net (code "13") (name "Net-(U3-VREG)") (class "Default")
      (node (ref "C108") (pin "2") (pinfunction "2_2") (pintype "passive"))
      (node (ref "U3") (pin "8") (pinfunction "VREG_8") (pintype "power_in"))
    )
    (net (code "14") (name "VIN") (class "Default")
      (node (ref "C104") (pin "1") (pinfunction "1_1") (pintype "passive"))
      (node (ref "C99") (pin "1") (pinfunction "1_1") (pintype "passive"))
      (node (ref "U2") (pin "10") (pinfunction "VIN_10") (pintype "power_in"))
      (node (ref "U2") (pin "9") (pinfunction "VIN_9") (pintype "power_in"))
      (node (ref "U3") (pin "10") (pinfunction "VIN_10") (pintype "power_in"))
      (node (ref "U3") (pin "9") (pinfunction "VIN_9") (pintype "power_in"))
    )
  )
)
